# shield-V1p2.net
KiCad netlist of a schematic drawn in EAGLE
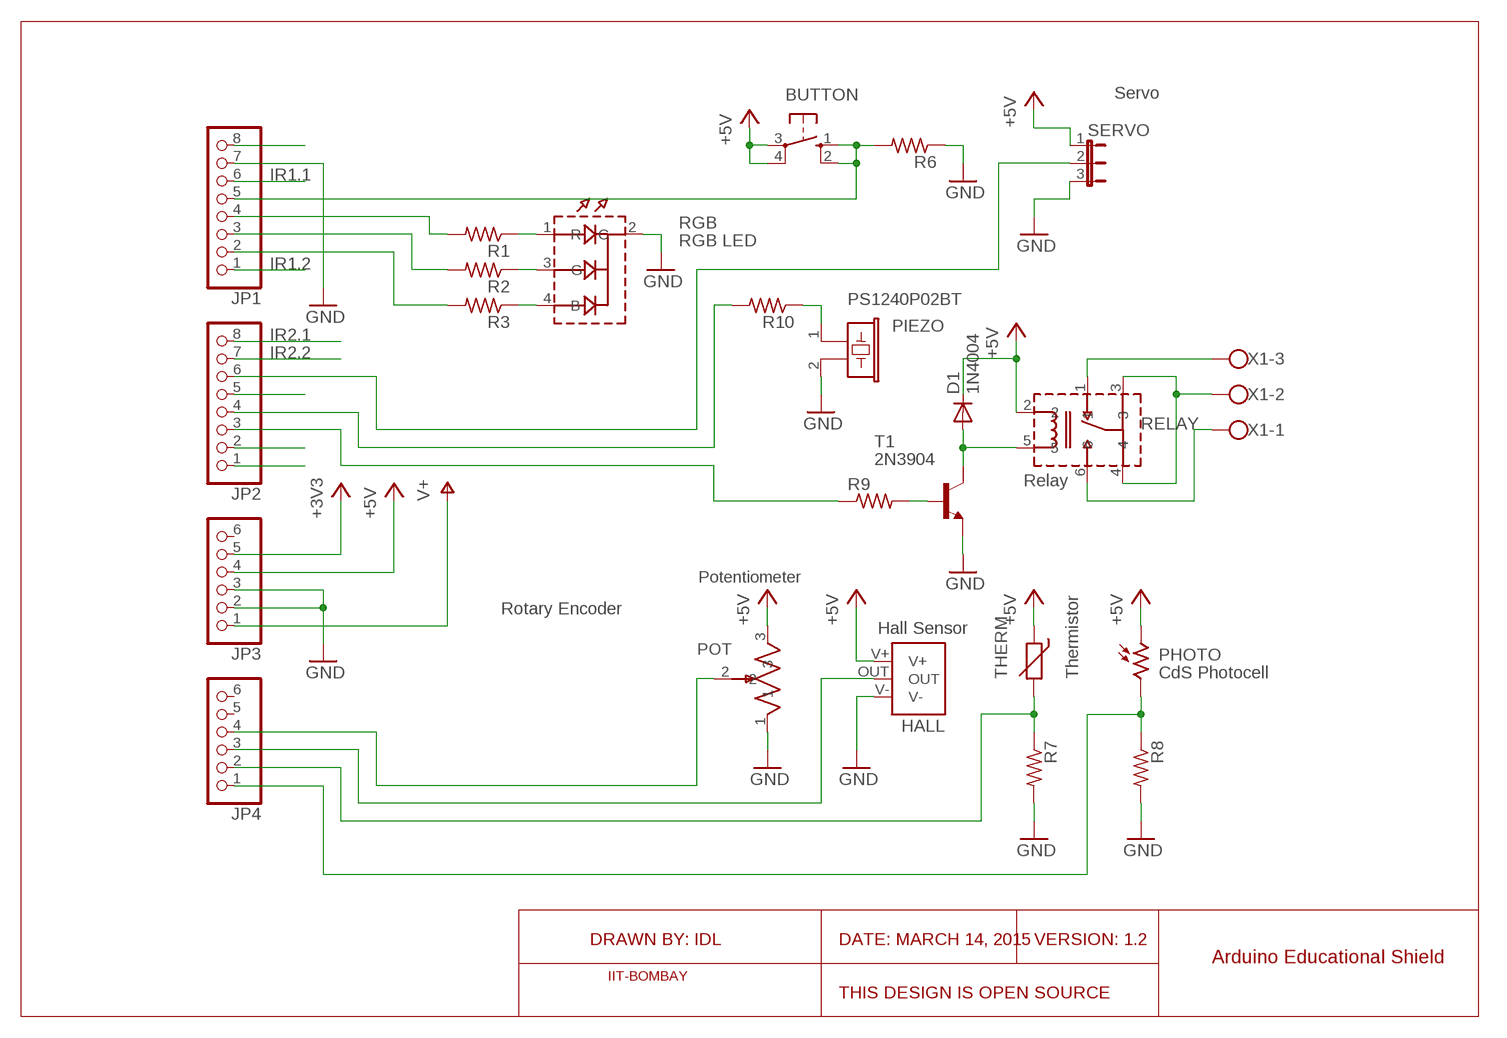
[diagram p0: schematic, sheet 1]

(export (version "E")
  (design (tool "Eeschema 10.0.6"))
  (components
    (comp (ref "BUTTON")
      (value "10-XX")
      (footprint "eagle-import:B3F-10XX")
      (libsource (lib "eagle-import") (part "10-XX"))
    )
    (comp (ref "D1")
      (value "1N4004")
      (footprint "eagle-import:DO41-10")
      (libsource (lib "eagle-import") (part "1N4004"))
    )
    (comp (ref "HALL")
      (value "SS49E")
      (footprint "eagle-import:TO_92_SHORT")
      (libsource (lib "eagle-import") (part "SS49E"))
    )
    (comp (ref "JP1")
      (value "PINHD-1X8")
      (footprint "eagle-import:1X08")
      (libsource (lib "eagle-import") (part "PINHD-1X8"))
    )
    (comp (ref "JP2")
      (value "PINHD-1X8")
      (footprint "eagle-import:1X08")
      (libsource (lib "eagle-import") (part "PINHD-1X8"))
    )
    (comp (ref "JP3")
      (value "PINHD-1X6")
      (footprint "eagle-import:1X06")
      (libsource (lib "eagle-import") (part "PINHD-1X6"))
    )
    (comp (ref "JP4")
      (value "PINHD-1X6")
      (footprint "eagle-import:1X06")
      (libsource (lib "eagle-import") (part "PINHD-1X6"))
    )
    (comp (ref "PHOTO")
      (value "CdS Photocell")
      (footprint "eagle-import:TO46-VT200")
      (libsource (lib "eagle-import") (part "VT20N1"))
    )
    (comp (ref "PIEZO")
      (value "PS1240P02BT")
      (footprint "eagle-import:PS1240P02BT")
      (libsource (lib "eagle-import") (part "PS1240P02BT"))
    )
    (comp (ref "POT")
      (value "EVU_POTENTIOMETER")
      (footprint "eagle-import:VERT_POT")
      (libsource (lib "eagle-import") (part "EVU_POTENTIOMETER"))
    )
    (comp (ref "R1")
      (value "R-US_0207/10")
      (footprint "eagle-import:0207_10")
      (libsource (lib "eagle-import") (part "R-US_0207/10"))
    )
    (comp (ref "R2")
      (value "R-US_0207/10")
      (footprint "eagle-import:0207_10")
      (libsource (lib "eagle-import") (part "R-US_0207/10"))
    )
    (comp (ref "R3")
      (value "R-US_0207/10")
      (footprint "eagle-import:0207_10")
      (libsource (lib "eagle-import") (part "R-US_0207/10"))
    )
    (comp (ref "R6")
      (value "R-US_0207/10")
      (footprint "eagle-import:0207_10")
      (libsource (lib "eagle-import") (part "R-US_0207/10"))
    )
    (comp (ref "R7")
      (value "R-US_0207/10")
      (footprint "eagle-import:0207_10")
      (libsource (lib "eagle-import") (part "R-US_0207/10"))
    )
    (comp (ref "R8")
      (value "R-US_0207/10")
      (footprint "eagle-import:0207_10")
      (libsource (lib "eagle-import") (part "R-US_0207/10"))
    )
    (comp (ref "R9")
      (value "R-US_0207/10")
      (footprint "eagle-import:0207_10")
      (libsource (lib "eagle-import") (part "R-US_0207/10"))
    )
    (comp (ref "R10")
      (value "R-US_0207/10")
      (footprint "eagle-import:0207_10")
      (libsource (lib "eagle-import") (part "R-US_0207/10"))
    )
    (comp (ref "RELAY")
      (value "TSC_1FORMC")
      (footprint "eagle-import:TSC_RELAY")
      (libsource (lib "eagle-import") (part "TSC_1FORMC"))
    )
    (comp (ref "RGB")
      (value "RGB LED")
      (footprint "eagle-import:RGB_VERTICAL")
      (libsource (lib "eagle-import") (part "RGBLED_COMMON_CATHODE"))
    )
    (comp (ref "SERVO")
      (value "JP2E")
      (footprint "eagle-import:JP2")
      (libsource (lib "eagle-import") (part "JP2E"))
    )
    (comp (ref "T1")
      (value "2N3904")
      (footprint "eagle-import:TO92")
      (libsource (lib "eagle-import") (part "2N3904"))
    )
    (comp (ref "THERM")
      (value "Thermistor")
      (footprint "eagle-import:R-5")
      (libsource (lib "eagle-import") (part "THERMISTOR-5"))
    )
    (comp (ref "X1")
      (value "W237-103")
      (footprint "eagle-import:W237-103")
      (libsource (lib "eagle-import") (part "W237-103"))
    )
  )
  (nets
    (net (code "1") (name "+3V3") (class "Default")
      (node (ref "JP3") (pin "5") (pinfunction "5_5") (pintype "passive"))
    )
    (net (code "2") (name "+5V") (class "Default")
      (node (ref "BUTTON") (pin "3") (pinfunction "P_3") (pintype "passive"))
      (node (ref "BUTTON") (pin "4") (pinfunction "P1_4") (pintype "passive"))
      (node (ref "D1") (pin "C") (pinfunction "C_C") (pintype "passive"))
      (node (ref "HALL") (pin "V+") (pinfunction "V+_V+") (pintype "bidirectional"))
      (node (ref "JP3") (pin "4") (pinfunction "4_4") (pintype "passive"))
      (node (ref "PHOTO") (pin "1") (pinfunction "1_1") (pintype "passive"))
      (node (ref "POT") (pin "3") (pinfunction "3_3") (pintype "bidirectional"))
      (node (ref "RELAY") (pin "2") (pinfunction "2_2") (pintype "bidirectional"))
      (node (ref "SERVO") (pin "1") (pinfunction "1_1") (pintype "passive"))
      (node (ref "THERM") (pin "1") (pinfunction "1_1") (pintype "passive"))
    )
    (net (code "3") (name "/IR1.1") (class "Default")
      (node (ref "JP1") (pin "6") (pinfunction "6_6") (pintype "passive"))
    )
    (net (code "4") (name "/IR1.2") (class "Default")
      (node (ref "JP1") (pin "1") (pinfunction "1_1") (pintype "passive"))
    )
    (net (code "5") (name "/IR2.1") (class "Default")
      (node (ref "JP2") (pin "8") (pinfunction "8_8") (pintype "passive"))
    )
    (net (code "6") (name "/IR2.2") (class "Default")
      (node (ref "JP2") (pin "7") (pinfunction "7_7") (pintype "passive"))
    )
    (net (code "7") (name "GND") (class "Default")
      (node (ref "HALL") (pin "V-") (pinfunction "V-_V-") (pintype "bidirectional"))
      (node (ref "JP1") (pin "7") (pinfunction "7_7") (pintype "passive"))
      (node (ref "JP3") (pin "2") (pinfunction "2_2") (pintype "passive"))
      (node (ref "JP3") (pin "3") (pinfunction "3_3") (pintype "passive"))
      (node (ref "PIEZO") (pin "2") (pinfunction "2_2") (pintype "passive"))
      (node (ref "POT") (pin "1") (pinfunction "1_1") (pintype "bidirectional"))
      (node (ref "R6") (pin "1") (pinfunction "1_1") (pintype "passive"))
      (node (ref "R7") (pin "2") (pinfunction "2_2") (pintype "passive"))
      (node (ref "R8") (pin "2") (pinfunction "2_2") (pintype "passive"))
      (node (ref "RGB") (pin "2") (pinfunction "C_2") (pintype "bidirectional"))
      (node (ref "SERVO") (pin "3") (pinfunction "3_3") (pintype "passive"))
      (node (ref "T1") (pin "3") (pinfunction "E_3") (pintype "passive"))
    )
    (net (code "8") (name "Net-(BUTTON-S)") (class "Default")
      (node (ref "BUTTON") (pin "1") (pinfunction "S_1") (pintype "passive"))
      (node (ref "BUTTON") (pin "2") (pinfunction "S1_2") (pintype "passive"))
      (node (ref "JP1") (pin "5") (pinfunction "5_5") (pintype "passive"))
      (node (ref "R6") (pin "2") (pinfunction "2_2") (pintype "passive"))
    )
    (net (code "9") (name "Net-(HALL-PadOUT)") (class "Default")
      (node (ref "HALL") (pin "OUT") (pinfunction "OUT_OUT") (pintype "bidirectional"))
      (node (ref "JP4") (pin "3") (pinfunction "3_3") (pintype "passive"))
    )
    (net (code "10") (name "Net-(JP1-Pad2)") (class "Default")
      (node (ref "JP1") (pin "2") (pinfunction "2_2") (pintype "passive"))
      (node (ref "R3") (pin "2") (pinfunction "2_2") (pintype "passive"))
    )
    (net (code "11") (name "Net-(JP1-Pad3)") (class "Default")
      (node (ref "JP1") (pin "3") (pinfunction "3_3") (pintype "passive"))
      (node (ref "R2") (pin "2") (pinfunction "2_2") (pintype "passive"))
    )
    (net (code "12") (name "Net-(JP1-Pad4)") (class "Default")
      (node (ref "JP1") (pin "4") (pinfunction "4_4") (pintype "passive"))
      (node (ref "R1") (pin "2") (pinfunction "2_2") (pintype "passive"))
    )
    (net (code "13") (name "Net-(JP2-Pad3)") (class "Default")
      (node (ref "JP2") (pin "3") (pinfunction "3_3") (pintype "passive"))
      (node (ref "R9") (pin "1") (pinfunction "1_1") (pintype "passive"))
    )
    (net (code "14") (name "Net-(JP2-Pad4)") (class "Default")
      (node (ref "JP2") (pin "4") (pinfunction "4_4") (pintype "passive"))
      (node (ref "R10") (pin "2") (pinfunction "2_2") (pintype "passive"))
    )
    (net (code "15") (name "Net-(JP2-Pad6)") (class "Default")
      (node (ref "JP2") (pin "6") (pinfunction "6_6") (pintype "passive"))
      (node (ref "SERVO") (pin "2") (pinfunction "2_2") (pintype "passive"))
    )
    (net (code "16") (name "Net-(JP4-Pad1)") (class "Default")
      (node (ref "JP4") (pin "1") (pinfunction "1_1") (pintype "passive"))
      (node (ref "PHOTO") (pin "2") (pinfunction "2_2") (pintype "passive"))
      (node (ref "R8") (pin "1") (pinfunction "1_1") (pintype "passive"))
    )
    (net (code "17") (name "Net-(JP4-Pad2)") (class "Default")
      (node (ref "JP4") (pin "2") (pinfunction "2_2") (pintype "passive"))
      (node (ref "R7") (pin "1") (pinfunction "1_1") (pintype "passive"))
      (node (ref "THERM") (pin "2") (pinfunction "2_2") (pintype "passive"))
    )
    (net (code "18") (name "Net-(JP4-Pad4)") (class "Default")
      (node (ref "JP4") (pin "4") (pinfunction "4_4") (pintype "passive"))
      (node (ref "POT") (pin "2") (pinfunction "2_2") (pintype "bidirectional"))
    )
    (net (code "19") (name "Net-(PIEZO-Pad1)") (class "Default")
      (node (ref "PIEZO") (pin "1") (pinfunction "1_1") (pintype "passive"))
      (node (ref "R10") (pin "1") (pinfunction "1_1") (pintype "passive"))
    )
    (net (code "20") (name "Net-(RGB-B)") (class "Default")
      (node (ref "R3") (pin "1") (pinfunction "1_1") (pintype "passive"))
      (node (ref "RGB") (pin "4") (pinfunction "B_4") (pintype "bidirectional"))
    )
    (net (code "21") (name "Net-(RGB-G)") (class "Default")
      (node (ref "R2") (pin "1") (pinfunction "1_1") (pintype "passive"))
      (node (ref "RGB") (pin "3") (pinfunction "G_3") (pintype "bidirectional"))
    )
    (net (code "22") (name "Net-(RGB-R)") (class "Default")
      (node (ref "R1") (pin "1") (pinfunction "1_1") (pintype "passive"))
      (node (ref "RGB") (pin "1") (pinfunction "R_1") (pintype "bidirectional"))
    )
    (net (code "23") (name "Net-(T1-B)") (class "Default")
      (node (ref "R9") (pin "2") (pinfunction "2_2") (pintype "passive"))
      (node (ref "T1") (pin "2") (pinfunction "B_2") (pintype "passive"))
    )
    (net (code "24") (name "Net-(T1-C)") (class "Default")
      (node (ref "D1") (pin "A") (pinfunction "A_A") (pintype "passive"))
      (node (ref "RELAY") (pin "5") (pinfunction "5_5") (pintype "bidirectional"))
      (node (ref "T1") (pin "1") (pinfunction "C_1") (pintype "passive"))
    )
    (net (code "25") (name "Net-(X1A-KL)") (class "Default")
      (node (ref "RELAY") (pin "6") (pinfunction "6_6") (pintype "bidirectional"))
      (node (ref "X1") (pin "1") (pinfunction "KL_1") (pintype "passive"))
    )
    (net (code "26") (name "Net-(X1B-KL)") (class "Default")
      (node (ref "RELAY") (pin "3") (pinfunction "3_3") (pintype "bidirectional"))
      (node (ref "RELAY") (pin "4") (pinfunction "4_4") (pintype "bidirectional"))
      (node (ref "X1") (pin "2") (pinfunction "KL_2") (pintype "passive"))
    )
    (net (code "27") (name "Net-(X1C-KL)") (class "Default")
      (node (ref "RELAY") (pin "1") (pinfunction "1_1") (pintype "bidirectional"))
      (node (ref "X1") (pin "3") (pinfunction "KL_3") (pintype "passive"))
    )
    (net (code "28") (name "V+") (class "Default")
      (node (ref "JP3") (pin "1") (pinfunction "1_1") (pintype "passive"))
    )
    (net (code "29") (name "unconnected-(JP1-Pad8)") (class "Default")
      (node (ref "JP1") (pin "8") (pinfunction "8_8") (pintype "passive"))
    )
    (net (code "30") (name "unconnected-(JP2-Pad1)") (class "Default")
      (node (ref "JP2") (pin "1") (pinfunction "1_1") (pintype "passive"))
    )
    (net (code "31") (name "unconnected-(JP2-Pad2)") (class "Default")
      (node (ref "JP2") (pin "2") (pinfunction "2_2") (pintype "passive"))
    )
    (net (code "32") (name "unconnected-(JP2-Pad5)") (class "Default")
      (node (ref "JP2") (pin "5") (pinfunction "5_5") (pintype "passive"))
    )
    (net (code "33") (name "unconnected-(JP3-Pad6)") (class "Default")
      (node (ref "JP3") (pin "6") (pinfunction "6_6") (pintype "passive"))
    )
    (net (code "34") (name "unconnected-(JP4-Pad5)") (class "Default")
      (node (ref "JP4") (pin "5") (pinfunction "5_5") (pintype "passive"))
    )
    (net (code "35") (name "unconnected-(JP4-Pad6)") (class "Default")
      (node (ref "JP4") (pin "6") (pinfunction "6_6") (pintype "passive"))
    )
  )
)
